# Addon-mapleCUx_Raspi-3V3-UART-Adapter-00.net
KiCad netlist of a schematic drawn in EAGLE
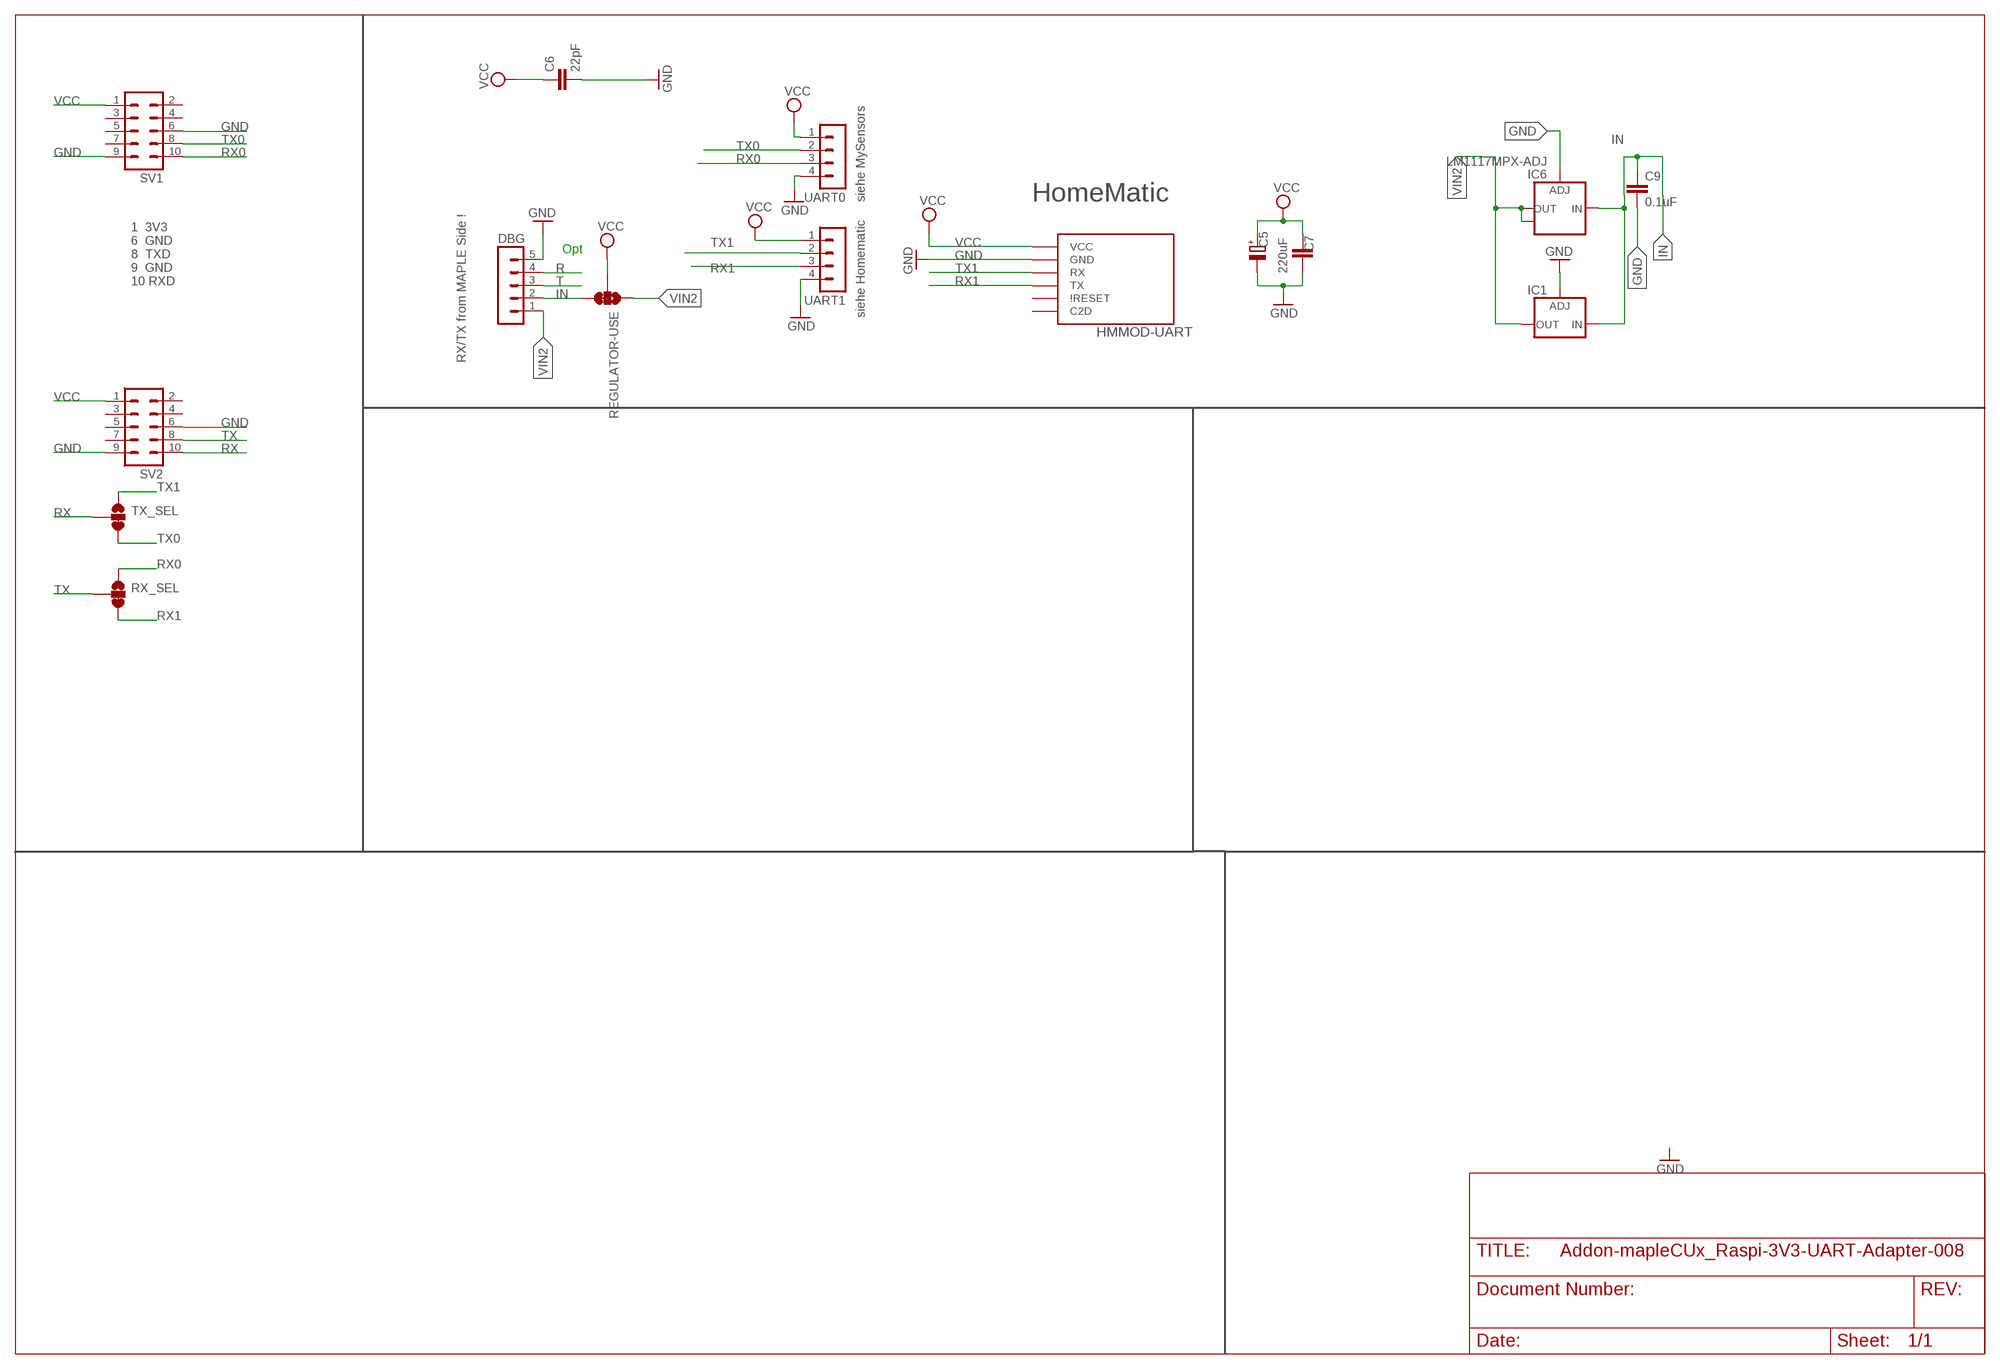
[diagram p0: schematic, sheet 1]

(export (version "E")
  (design (tool "Eeschema 10.0.6"))
  (components
    (comp (ref "C5")
      (value "220uF")
      (footprint "eagle-import:E5-8,5")
      (libsource (lib "eagle-import") (part "CPOL-EUE5-8.5"))
    )
    (comp (ref "C6")
      (value "22pF")
      (footprint "eagle-import:C0805")
      (libsource (lib "eagle-import") (part "C-EUC0805"))
    )
    (comp (ref "C7")
      (value "C-EUC1812")
      (footprint "eagle-import:C1812")
      (libsource (lib "eagle-import") (part "C-EUC1812"))
    )
    (comp (ref "C9")
      (value "0.1uF")
      (footprint "eagle-import:C1206")
      (libsource (lib "eagle-import") (part "C-EUC1206"))
    )
    (comp (ref "DBG")
      (value "MA05-1")
      (footprint "eagle-import:MA05-1")
      (libsource (lib "eagle-import") (part "MA05-1"))
    )
    (comp (ref "HMMOD-UART")
      (value "HM-MOD-UARTDIL")
      (footprint "eagle-import:HM-MOD-UART-DIL")
      (libsource (lib "eagle-import") (part "HM-MOD-UARTDIL"))
    )
    (comp (ref "IC1")
      (value "LD117ADT50TR")
      (footprint "eagle-import:DPACK")
      (libsource (lib "eagle-import") (part "LD117A?DT50TR"))
    )
    (comp (ref "IC6")
      (value "LM1117MPX-ADJ")
      (footprint "eagle-import:SOT223")
      (libsource (lib "eagle-import") (part "LM1117MPX-ADJ"))
    )
    (comp (ref "REGULATOR-USE")
      (value "JUMPER-SMT_3_1-NC_TRACE_SILK")
      (footprint "eagle-import:SMT-JUMPER_3_1-NC_TRACE_SILK")
      (libsource (lib "eagle-import") (part "JUMPER-SMT_3_1-NC_TRACE_SILK"))
    )
    (comp (ref "RX_SEL")
      (value "JUMPER-SMT_3_1-NC_TRACE_SILK")
      (footprint "eagle-import:SMT-JUMPER_3_1-NC_TRACE_SILK")
      (libsource (lib "eagle-import") (part "JUMPER-SMT_3_1-NC_TRACE_SILK"))
    )
    (comp (ref "SV1")
      (value "MA05-2")
      (footprint "eagle-import:MA05-2")
      (libsource (lib "eagle-import") (part "MA05-2"))
    )
    (comp (ref "SV2")
      (value "MA05-2")
      (footprint "eagle-import:MA05-2")
      (libsource (lib "eagle-import") (part "MA05-2"))
    )
    (comp (ref "TX_SEL")
      (value "JUMPER-SMT_3_1-NC_TRACE_SILK")
      (footprint "eagle-import:SMT-JUMPER_3_1-NC_TRACE_SILK")
      (libsource (lib "eagle-import") (part "JUMPER-SMT_3_1-NC_TRACE_SILK"))
    )
    (comp (ref "UART0")
      (value "MA04-1")
      (footprint "eagle-import:MA04-1")
      (libsource (lib "eagle-import") (part "MA04-1"))
    )
    (comp (ref "UART1")
      (value "MA04-1")
      (footprint "eagle-import:MA04-1")
      (libsource (lib "eagle-import") (part "MA04-1"))
    )
  )
  (nets
    (net (code "1") (name "/R") (class "Default")
      (node (ref "DBG") (pin "4") (pinfunction "4_4") (pintype "passive"))
    )
    (net (code "2") (name "/RX") (class "Default")
      (node (ref "SV2") (pin "10") (pinfunction "10_10") (pintype "passive"))
      (node (ref "TX_SEL") (pin "2") (pinfunction "2_2") (pintype "passive"))
    )
    (net (code "3") (name "/RX0") (class "Default")
      (node (ref "RX_SEL") (pin "1") (pinfunction "1_1") (pintype "passive"))
      (node (ref "SV1") (pin "10") (pinfunction "10_10") (pintype "passive"))
      (node (ref "UART0") (pin "3") (pinfunction "3_3") (pintype "passive"))
    )
    (net (code "4") (name "/RX1") (class "Default")
      (node (ref "HMMOD-UART") (pin "5") (pinfunction "TX_5") (pintype "bidirectional"))
      (node (ref "RX_SEL") (pin "3") (pinfunction "3_3") (pintype "passive"))
      (node (ref "UART1") (pin "3") (pinfunction "3_3") (pintype "passive"))
    )
    (net (code "5") (name "/T") (class "Default")
      (node (ref "DBG") (pin "3") (pinfunction "3_3") (pintype "passive"))
    )
    (net (code "6") (name "/TX") (class "Default")
      (node (ref "RX_SEL") (pin "2") (pinfunction "2_2") (pintype "passive"))
      (node (ref "SV2") (pin "8") (pinfunction "8_8") (pintype "passive"))
    )
    (net (code "7") (name "/TX0") (class "Default")
      (node (ref "SV1") (pin "8") (pinfunction "8_8") (pintype "passive"))
      (node (ref "TX_SEL") (pin "3") (pinfunction "3_3") (pintype "passive"))
      (node (ref "UART0") (pin "2") (pinfunction "2_2") (pintype "passive"))
    )
    (net (code "8") (name "/TX1") (class "Default")
      (node (ref "HMMOD-UART") (pin "6") (pinfunction "RX_6") (pintype "bidirectional"))
      (node (ref "TX_SEL") (pin "1") (pinfunction "1_1") (pintype "passive"))
      (node (ref "UART1") (pin "2") (pinfunction "2_2") (pintype "passive"))
    )
    (net (code "9") (name "GND") (class "Default")
      (node (ref "C5") (pin "-") (pinfunction "-_-") (pintype "passive"))
      (node (ref "C6") (pin "2") (pinfunction "2_2") (pintype "passive"))
      (node (ref "C7") (pin "1") (pinfunction "1_1") (pintype "passive"))
      (node (ref "C9") (pin "2") (pinfunction "2_2") (pintype "passive"))
      (node (ref "DBG") (pin "5") (pinfunction "5_5") (pintype "passive"))
      (node (ref "HMMOD-UART") (pin "2") (pinfunction "GND_2") (pintype "power_in"))
      (node (ref "IC1") (pin "1") (pinfunction "ADJ_1") (pintype "input"))
      (node (ref "IC6") (pin "1") (pinfunction "ADJ_1") (pintype "input"))
      (node (ref "SV1") (pin "6") (pinfunction "6_6") (pintype "passive"))
      (node (ref "SV1") (pin "9") (pinfunction "9_9") (pintype "passive"))
      (node (ref "SV2") (pin "6") (pinfunction "6_6") (pintype "passive"))
      (node (ref "SV2") (pin "9") (pinfunction "9_9") (pintype "passive"))
      (node (ref "UART0") (pin "4") (pinfunction "4_4") (pintype "passive"))
      (node (ref "UART1") (pin "4") (pinfunction "4_4") (pintype "passive"))
    )
    (net (code "10") (name "IN") (class "Default")
      (node (ref "C9") (pin "1") (pinfunction "1_1") (pintype "passive"))
      (node (ref "DBG") (pin "2") (pinfunction "2_2") (pintype "passive"))
      (node (ref "IC1") (pin "3") (pinfunction "IN_3") (pintype "input"))
      (node (ref "IC6") (pin "3") (pinfunction "IN_3") (pintype "input"))
      (node (ref "REGULATOR-USE") (pin "3") (pinfunction "3_3") (pintype "passive"))
    )
    (net (code "11") (name "VCC") (class "Default")
      (node (ref "C5") (pin "+") (pinfunction "+_+") (pintype "passive"))
      (node (ref "C6") (pin "1") (pinfunction "1_1") (pintype "passive"))
      (node (ref "C7") (pin "2") (pinfunction "2_2") (pintype "passive"))
      (node (ref "HMMOD-UART") (pin "1") (pinfunction "VCC_1") (pintype "power_in"))
      (node (ref "REGULATOR-USE") (pin "2") (pinfunction "2_2") (pintype "passive"))
      (node (ref "SV1") (pin "1") (pinfunction "1_1") (pintype "passive"))
      (node (ref "SV2") (pin "1") (pinfunction "1_1") (pintype "passive"))
      (node (ref "UART0") (pin "1") (pinfunction "1_1") (pintype "passive"))
      (node (ref "UART1") (pin "1") (pinfunction "1_1") (pintype "passive"))
    )
    (net (code "12") (name "VIN2") (class "Default")
      (node (ref "DBG") (pin "1") (pinfunction "1_1") (pintype "passive"))
      (node (ref "IC1") (pin "4") (pinfunction "OUT_4") (pintype "passive"))
      (node (ref "IC6") (pin "2") (pinfunction "OUT_2") (pintype "passive"))
      (node (ref "IC6") (pin "TAB") (pinfunction "OUT1_TAB") (pintype "passive"))
      (node (ref "REGULATOR-USE") (pin "1") (pinfunction "1_1") (pintype "passive"))
    )
    (net (code "13") (name "unconnected-(HMMOD-UART-C2D-Pad3)") (class "Default")
      (node (ref "HMMOD-UART") (pin "3") (pinfunction "C2D_3") (pintype "bidirectional"))
    )
    (net (code "14") (name "unconnected-(HMMOD-UART-\\~{RESET}-Pad4)") (class "Default")
      (node (ref "HMMOD-UART") (pin "4") (pinfunction "\\~{RESET}_4") (pintype "bidirectional"))
    )
    (net (code "15") (name "unconnected-(SV1-Pad2)") (class "Default")
      (node (ref "SV1") (pin "2") (pinfunction "2_2") (pintype "passive"))
    )
    (net (code "16") (name "unconnected-(SV1-Pad3)") (class "Default")
      (node (ref "SV1") (pin "3") (pinfunction "3_3") (pintype "passive"))
    )
    (net (code "17") (name "unconnected-(SV1-Pad4)") (class "Default")
      (node (ref "SV1") (pin "4") (pinfunction "4_4") (pintype "passive"))
    )
    (net (code "18") (name "unconnected-(SV1-Pad5)") (class "Default")
      (node (ref "SV1") (pin "5") (pinfunction "5_5") (pintype "passive"))
    )
    (net (code "19") (name "unconnected-(SV1-Pad7)") (class "Default")
      (node (ref "SV1") (pin "7") (pinfunction "7_7") (pintype "passive"))
    )
    (net (code "20") (name "unconnected-(SV2-Pad2)") (class "Default")
      (node (ref "SV2") (pin "2") (pinfunction "2_2") (pintype "passive"))
    )
    (net (code "21") (name "unconnected-(SV2-Pad3)") (class "Default")
      (node (ref "SV2") (pin "3") (pinfunction "3_3") (pintype "passive"))
    )
    (net (code "22") (name "unconnected-(SV2-Pad4)") (class "Default")
      (node (ref "SV2") (pin "4") (pinfunction "4_4") (pintype "passive"))
    )
    (net (code "23") (name "unconnected-(SV2-Pad5)") (class "Default")
      (node (ref "SV2") (pin "5") (pinfunction "5_5") (pintype "passive"))
    )
    (net (code "24") (name "unconnected-(SV2-Pad7)") (class "Default")
      (node (ref "SV2") (pin "7") (pinfunction "7_7") (pintype "passive"))
    )
  )
)
